# CONNECTOR_B.net
KiCad netlist of a schematic drawn in Altium Designer
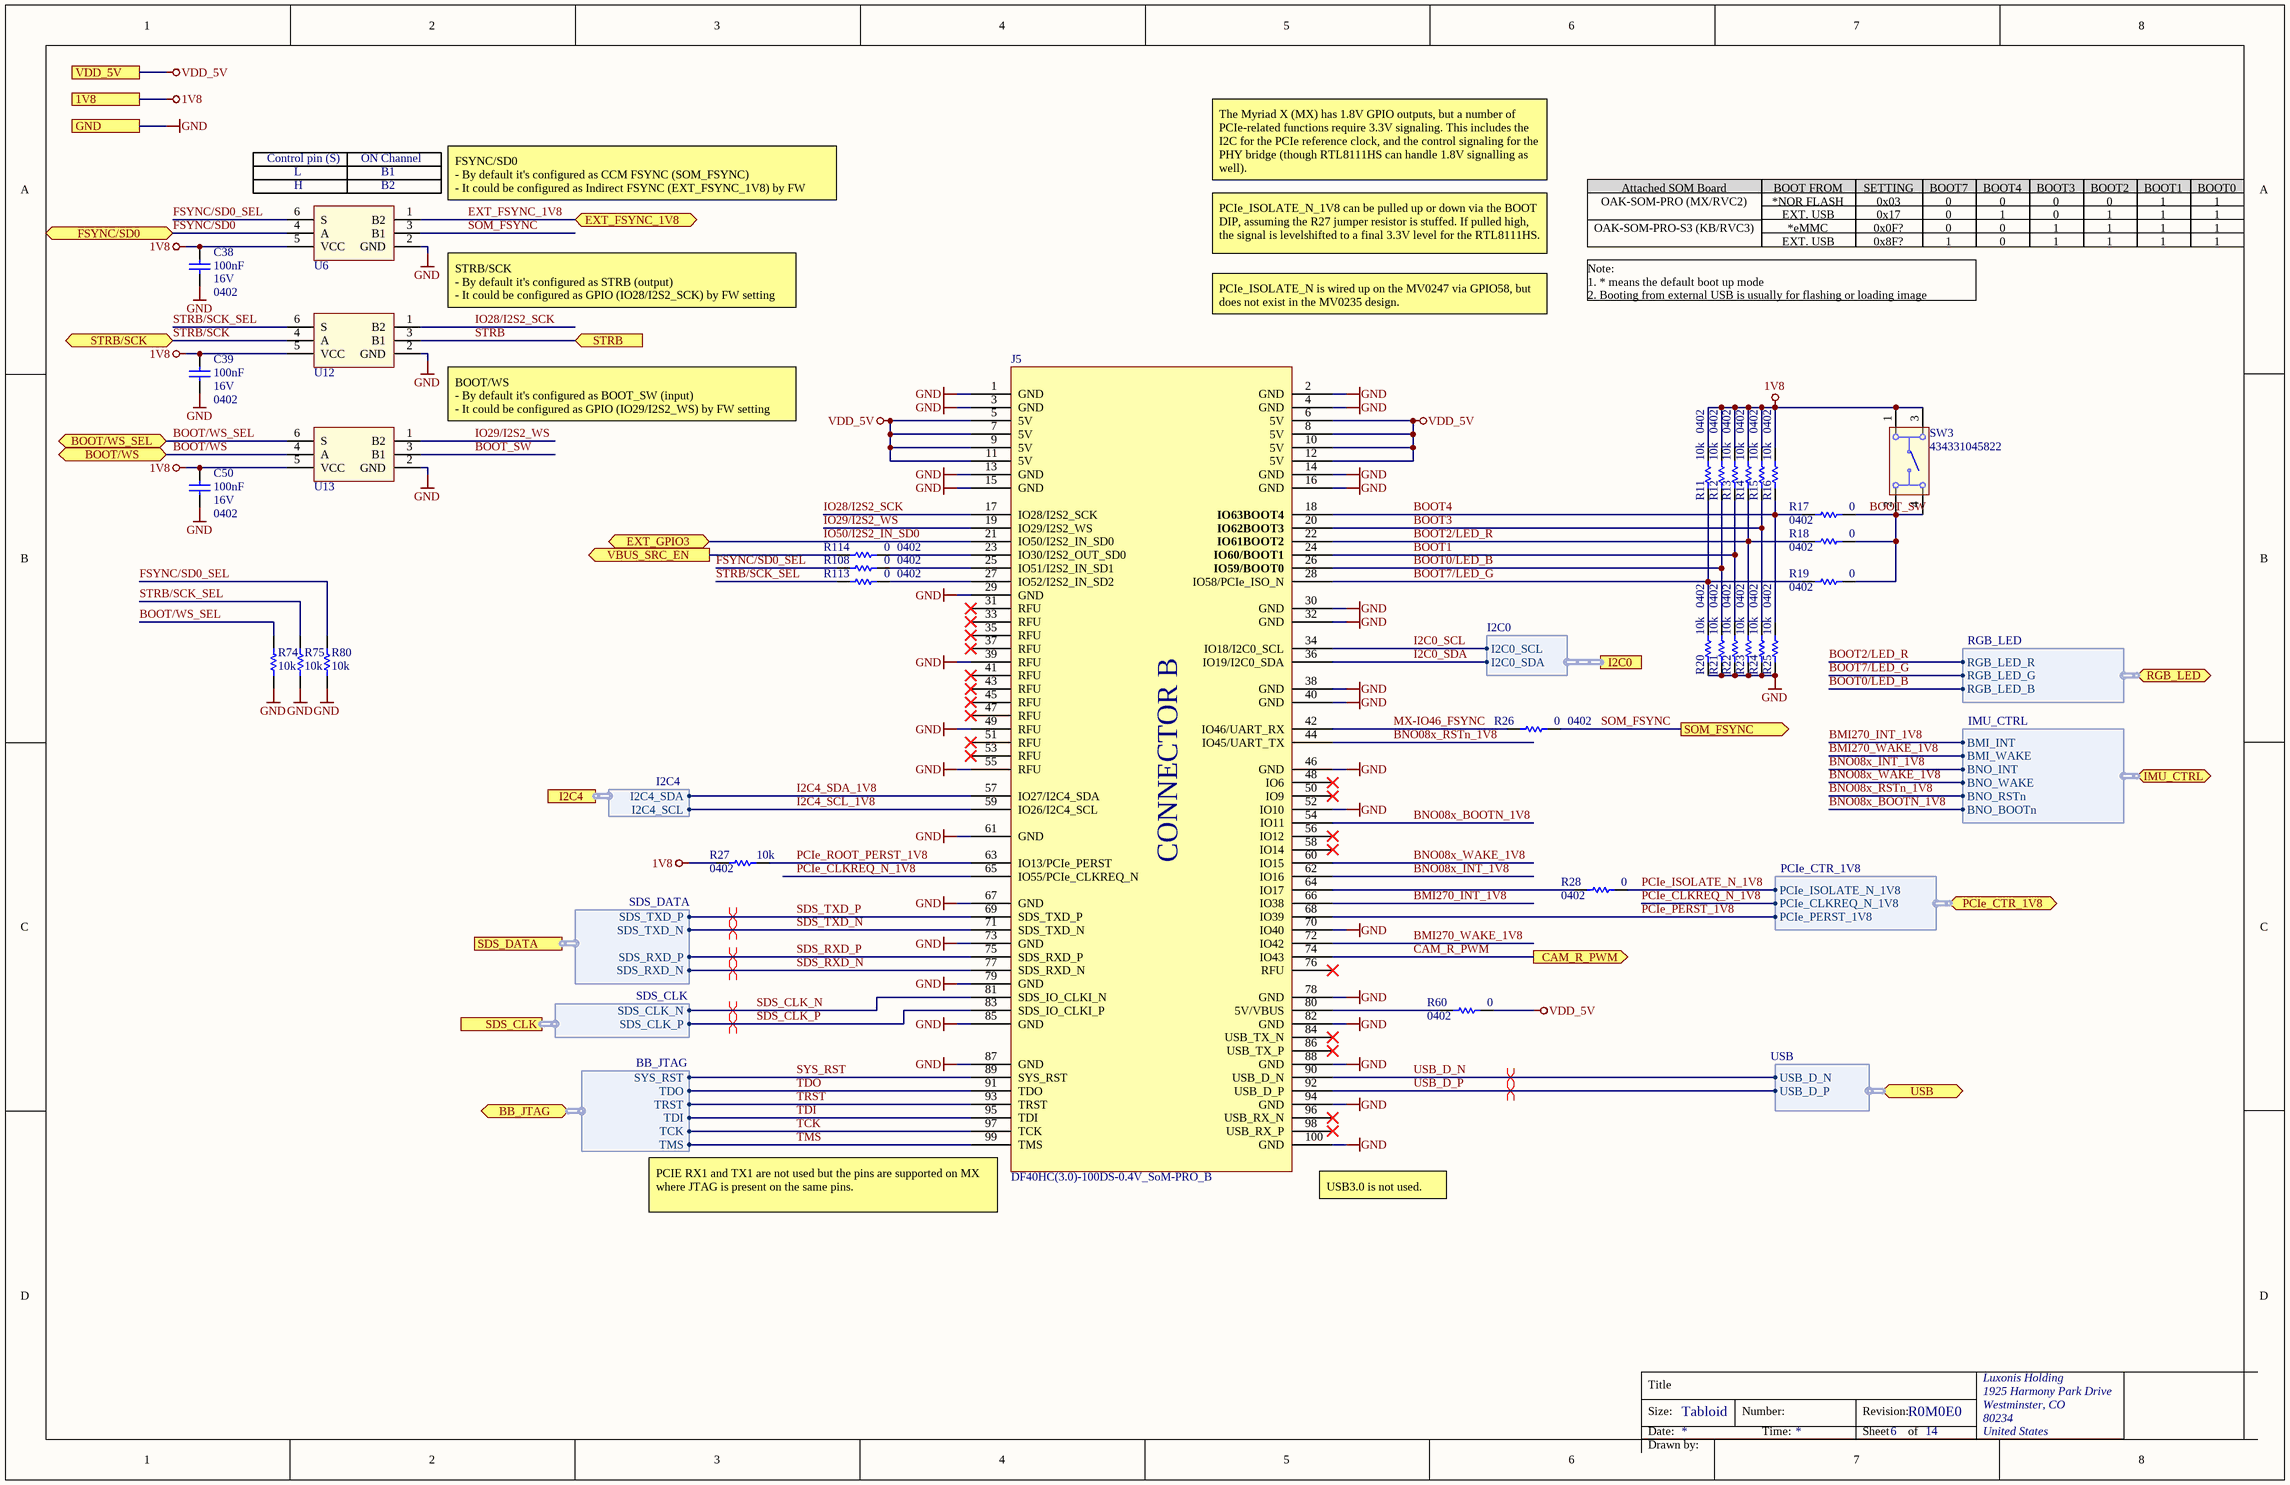
[diagram p0: CONNECTOR_B.SchDoc]

(export (version "E")
  (design (tool "Eeschema 10.0.6"))
  (components
    (comp (ref "C38")
      (value "100nF")
      (footprint "CAPC0402(1005)60_N")
      (description "CAP CER 0.1UF 16V X7R 0402 10%")
      (fields
        (field (name "VOLTAGE RATING") "16V")
        (field (name "CASE/PACKAGE") "0402")
        (field (name "TOLERANCE") "10%")
        (field (name "Comment") "CL05B104KO5NFNC")
      )
      (libsource (lib "Luxonis LLC") (part "GRM188R61C475KAAJD"))
    )
    (comp (ref "C39")
      (value "100nF")
      (footprint "CAPC0402(1005)60_N")
      (description "CAP CER 0.1UF 16V X7R 0402 10%")
      (fields
        (field (name "VOLTAGE RATING") "16V")
        (field (name "CASE/PACKAGE") "0402")
        (field (name "TOLERANCE") "10%")
        (field (name "Comment") "CL05B104KO5NFNC")
      )
      (libsource (lib "Luxonis LLC") (part "GRM188R61C475KAAJD"))
    )
    (comp (ref "C50")
      (value "100nF")
      (footprint "CAPC0402(1005)60_N")
      (description "CAP CER 0.1UF 16V X7R 0402 10%")
      (fields
        (field (name "VOLTAGE RATING") "16V")
        (field (name "CASE/PACKAGE") "0402")
        (field (name "TOLERANCE") "10%")
        (field (name "Comment") "CL05B104KO5NFNC")
      )
      (libsource (lib "Luxonis LLC") (part "GRM188R61C475KAAJD"))
    )
    (comp (ref "J5")
      (value "DF40HC(3.0)-100DS-0.4V_SoM-PRO_B")
      (footprint "CON_B_BW2099_SoM_DF40HC-3.0-100DS-0.4V_minpad")
      (description "OAK-SoM-Pro base board conn. B")
      (libsource (lib "Luxonis LLC") (part "DF40HC(3.0)-100DS-0.4V_SoM-PRO_B"))
    )
    (comp (ref "R11")
      (value "10k")
      (footprint "RESC0402(1005)_N")
      (description "RES SMD 10K OHM 1% 1/16W 0402")
      (fields
        (field (name "CASE/PACKAGE") "0402")
        (field (name "TOLERANCE") "1%")
        (field (name "Comment") "RC0402FR-1310KL")
      )
      (libsource (lib "Luxonis LLC") (part "RC0402FR-0722RL_1"))
    )
    (comp (ref "R12")
      (value "10k")
      (footprint "RESC0402(1005)_N")
      (description "RES SMD 10K OHM 1% 1/16W 0402")
      (fields
        (field (name "CASE/PACKAGE") "0402")
        (field (name "TOLERANCE") "1%")
        (field (name "Comment") "RC0402FR-1310KL")
      )
      (libsource (lib "Luxonis LLC") (part "RC0402FR-0722RL_1"))
    )
    (comp (ref "R13")
      (value "10k")
      (footprint "RESC0402(1005)_N")
      (description "RES SMD 10K OHM 1% 1/16W 0402")
      (fields
        (field (name "CASE/PACKAGE") "0402")
        (field (name "TOLERANCE") "1%")
        (field (name "Comment") "RC0402FR-1310KL")
      )
      (libsource (lib "Luxonis LLC") (part "RC0402FR-0722RL_1"))
    )
    (comp (ref "R14")
      (value "10k")
      (footprint "RESC0402(1005)_N")
      (description "RES SMD 10K OHM 1% 1/16W 0402")
      (fields
        (field (name "CASE/PACKAGE") "0402")
        (field (name "TOLERANCE") "1%")
        (field (name "Comment") "RC0402FR-1310KL")
      )
      (libsource (lib "Luxonis LLC") (part "RC0402FR-0722RL_1"))
    )
    (comp (ref "R15")
      (value "10k")
      (footprint "RESC0402(1005)_N")
      (description "RES SMD 10K OHM 1% 1/16W 0402")
      (fields
        (field (name "CASE/PACKAGE") "0402")
        (field (name "TOLERANCE") "1%")
        (field (name "Comment") "RC0402FR-1310KL")
      )
      (libsource (lib "Luxonis LLC") (part "RC0402FR-0722RL_1"))
    )
    (comp (ref "R16")
      (value "10k")
      (footprint "RESC0402(1005)_N")
      (description "RES SMD 10K OHM 1% 1/16W 0402")
      (fields
        (field (name "CASE/PACKAGE") "0402")
        (field (name "TOLERANCE") "1%")
        (field (name "Comment") "RC0402FR-1310KL")
      )
      (libsource (lib "Luxonis LLC") (part "RC0402FR-0722RL_1"))
    )
    (comp (ref "R17")
      (value "0")
      (footprint "RESC0402(1005)_L")
      (description "RES SMD 0 OHM 5% 1/16W 0402")
      (fields
        (field (name "CASE/PACKAGE") "0402")
        (field (name "TOLERANCE") "5%")
        (field (name "Comment") "CRCW04020000Z0ED")
      )
      (libsource (lib "Luxonis LLC") (part "Default resistor symbol"))
    )
    (comp (ref "R18")
      (value "0")
      (footprint "RESC0402(1005)_L")
      (description "RES SMD 0 OHM 5% 1/16W 0402")
      (fields
        (field (name "CASE/PACKAGE") "0402")
        (field (name "TOLERANCE") "5%")
        (field (name "Comment") "CRCW04020000Z0ED")
      )
      (libsource (lib "Luxonis LLC") (part "Default resistor symbol"))
    )
    (comp (ref "R19")
      (value "0")
      (footprint "RESC0402(1005)_L")
      (description "RES SMD 0 OHM 5% 1/16W 0402")
      (fields
        (field (name "CASE/PACKAGE") "0402")
        (field (name "TOLERANCE") "5%")
        (field (name "Comment") "CRCW04020000Z0ED")
      )
      (libsource (lib "Luxonis LLC") (part "Default resistor symbol"))
    )
    (comp (ref "R20")
      (value "10k")
      (footprint "RESC0402(1005)_N")
      (description "RES SMD 10K OHM 1% 1/16W 0402")
      (fields
        (field (name "CASE/PACKAGE") "0402")
        (field (name "TOLERANCE") "1%")
        (field (name "Comment") "RC0402FR-1310KL")
      )
      (libsource (lib "Luxonis LLC") (part "RC0402FR-0722RL_1"))
    )
    (comp (ref "R21")
      (value "10k")
      (footprint "RESC0402(1005)_N")
      (description "RES SMD 10K OHM 1% 1/16W 0402")
      (fields
        (field (name "CASE/PACKAGE") "0402")
        (field (name "TOLERANCE") "1%")
        (field (name "Comment") "RC0402FR-1310KL")
      )
      (libsource (lib "Luxonis LLC") (part "RC0402FR-0722RL_1"))
    )
    (comp (ref "R22")
      (value "10k")
      (footprint "RESC0402(1005)_N")
      (description "RES SMD 10K OHM 1% 1/16W 0402")
      (fields
        (field (name "CASE/PACKAGE") "0402")
        (field (name "TOLERANCE") "1%")
        (field (name "Comment") "RC0402FR-1310KL")
      )
      (libsource (lib "Luxonis LLC") (part "RC0402FR-0722RL_1"))
    )
    (comp (ref "R23")
      (value "10k")
      (footprint "RESC0402(1005)_N")
      (description "RES SMD 10K OHM 1% 1/16W 0402")
      (fields
        (field (name "CASE/PACKAGE") "0402")
        (field (name "TOLERANCE") "1%")
        (field (name "Comment") "RC0402FR-1310KL")
      )
      (libsource (lib "Luxonis LLC") (part "RC0402FR-0722RL_1"))
    )
    (comp (ref "R24")
      (value "10k")
      (footprint "RESC0402(1005)_N")
      (description "RES SMD 10K OHM 1% 1/16W 0402")
      (fields
        (field (name "CASE/PACKAGE") "0402")
        (field (name "TOLERANCE") "1%")
        (field (name "Comment") "RC0402FR-1310KL")
      )
      (libsource (lib "Luxonis LLC") (part "RC0402FR-0722RL_1"))
    )
    (comp (ref "R25")
      (value "10k")
      (footprint "RESC0402(1005)_N")
      (description "RES SMD 10K OHM 1% 1/16W 0402")
      (fields
        (field (name "CASE/PACKAGE") "0402")
        (field (name "TOLERANCE") "1%")
        (field (name "Comment") "RC0402FR-1310KL")
      )
      (libsource (lib "Luxonis LLC") (part "RC0402FR-0722RL_1"))
    )
    (comp (ref "R26")
      (value "0")
      (footprint "RESC0402(1005)_L")
      (description "RES SMD 0 OHM 5% 1/16W 0402")
      (fields
        (field (name "CASE/PACKAGE") "0402")
        (field (name "TOLERANCE") "5%")
        (field (name "Comment") "CRCW04020000Z0ED")
      )
      (libsource (lib "Luxonis LLC") (part "Default resistor symbol"))
    )
    (comp (ref "R27")
      (value "10k")
      (footprint "RESC0402(1005)_N")
      (description "RES SMD 10K OHM 1% 1/16W 0402")
      (fields
        (field (name "CASE/PACKAGE") "0402")
        (field (name "TOLERANCE") "1%")
        (field (name "Comment") "RC0402FR-1310KL")
      )
      (libsource (lib "Luxonis LLC") (part "RC0402FR-0722RL_1"))
    )
    (comp (ref "R28")
      (value "0")
      (footprint "RESC0402(1005)_L")
      (description "RES SMD 0 OHM 5% 1/16W 0402")
      (fields
        (field (name "CASE/PACKAGE") "0402")
        (field (name "TOLERANCE") "5%")
        (field (name "Comment") "CRCW04020000Z0ED")
      )
      (libsource (lib "Luxonis LLC") (part "Default resistor symbol"))
    )
    (comp (ref "R60")
      (value "0")
      (footprint "RESC0402(1005)_L")
      (description "RES SMD 0 OHM 5% 1/16W 0402")
      (fields
        (field (name "CASE/PACKAGE") "0402")
        (field (name "TOLERANCE") "5%")
        (field (name "Comment") "CRCW04020000Z0ED")
      )
      (libsource (lib "Luxonis LLC") (part "Default resistor symbol"))
    )
    (comp (ref "R74")
      (value "10k")
      (footprint "RESC0402(1005)_N")
      (description "RES SMD 10K OHM 1% 1/16W 0402")
      (fields (field (name "TOLERANCE") "1%") (field (name "Comment") "RC0402FR-1310KL"))
      (libsource (lib "Luxonis LLC") (part "RC0402FR-0722RL_1"))
    )
    (comp (ref "R75")
      (value "10k")
      (footprint "RESC0402(1005)_N")
      (description "RES SMD 10K OHM 1% 1/16W 0402")
      (fields (field (name "TOLERANCE") "1%") (field (name "Comment") "RC0402FR-1310KL"))
      (libsource (lib "Luxonis LLC") (part "RC0402FR-0722RL_1"))
    )
    (comp (ref "R80")
      (value "10k")
      (footprint "RESC0402(1005)_N")
      (description "RES SMD 10K OHM 1% 1/16W 0402")
      (fields (field (name "TOLERANCE") "1%") (field (name "Comment") "RC0402FR-1310KL"))
      (libsource (lib "Luxonis LLC") (part "RC0402FR-0722RL_1"))
    )
    (comp (ref "R108")
      (value "0")
      (footprint "RESC0402(1005)_L")
      (description "RES SMD 0 OHM 5% 1/16W 0402")
      (fields
        (field (name "CASE/PACKAGE") "0402")
        (field (name "TOLERANCE") "5%")
        (field (name "Comment") "CRCW04020000Z0ED")
      )
      (libsource (lib "Luxonis LLC") (part "Default resistor symbol"))
    )
    (comp (ref "R113")
      (value "0")
      (footprint "RESC0402(1005)_L")
      (description "RES SMD 0 OHM 5% 1/16W 0402")
      (fields
        (field (name "CASE/PACKAGE") "0402")
        (field (name "TOLERANCE") "5%")
        (field (name "Comment") "CRCW04020000Z0ED")
      )
      (libsource (lib "Luxonis LLC") (part "Default resistor symbol"))
    )
    (comp (ref "R114")
      (value "0")
      (footprint "RESC0402(1005)_L")
      (description "RES SMD 0 OHM 5% 1/16W 0402")
      (fields
        (field (name "CASE/PACKAGE") "0402")
        (field (name "TOLERANCE") "5%")
        (field (name "Comment") "CRCW04020000Z0ED")
      )
      (libsource (lib "Luxonis LLC") (part "Default resistor symbol"))
    )
    (comp (ref "SW3")
      (value "434331045822")
      (footprint "434331045822")
      (libsource (lib "Luxonis LLC") (part "WE-TACT-SW-4"))
    )
    (comp (ref "U6")
      (value "SN74LVC1G3157DCKR")
      (footprint "DCK6_65")
      (description "IC SWITCH SPDT SC70-6 1 Circuit IC Switch 2:1 15Ohm SC-70-6")
      (libsource (lib "Luxonis LLC") (part "SN74LVC1G3157DCKR"))
    )
    (comp (ref "U12")
      (value "SN74LVC1G3157DCKR")
      (footprint "DCK6_65")
      (description "IC SWITCH SPDT SC70-6 1 Circuit IC Switch 2:1 15Ohm SC-70-6")
      (libsource (lib "Luxonis LLC") (part "SN74LVC1G3157DCKR"))
    )
    (comp (ref "U13")
      (value "SN74LVC1G3157DCKR")
      (footprint "DCK6_65")
      (description "IC SWITCH SPDT SC70-6 1 Circuit IC Switch 2:1 15Ohm SC-70-6")
      (libsource (lib "Luxonis LLC") (part "SN74LVC1G3157DCKR"))
    )
  )
  (nets
    (net (code "10") (name "/BMI270_INT_1V8") (class "Default")
      (node (ref "J5") (pin "66") (pinfunction "IO38_66") (pintype "passive"))
    )
    (net (code "11") (name "/BMI270_WAKE_1V8") (class "Default")
      (node (ref "J5") (pin "72") (pinfunction "IO42_72") (pintype "passive"))
    )
    (net (code "12") (name "/BNO08x_BOOTN_1V8") (class "Default")
      (node (ref "J5") (pin "54") (pinfunction "IO11_54") (pintype "passive"))
    )
    (net (code "13") (name "/BNO08x_INT_1V8") (class "Default")
      (node (ref "J5") (pin "62") (pinfunction "IO16_62") (pintype "passive"))
    )
    (net (code "14") (name "/BNO08x_RSTn_1V8") (class "Default")
      (node (ref "J5") (pin "44") (pinfunction "IO45/UART_TX_44") (pintype "passive"))
    )
    (net (code "15") (name "/BNO08x_WAKE_1V8") (class "Default")
      (node (ref "J5") (pin "60") (pinfunction "IO15_60") (pintype "passive"))
    )
    (net (code "16") (name "/BOOT0{slash}LED_B") (class "Default")
      (node (ref "J5") (pin "26") (pinfunction "IO59/BOOT0_26") (pintype "passive"))
      (node (ref "R12") (pin "1") (pinfunction "1_1") (pintype "passive"))
      (node (ref "R21") (pin "2") (pinfunction "2_2") (pintype "passive"))
    )
    (net (code "17") (name "/BOOT1") (class "Default")
      (node (ref "J5") (pin "24") (pinfunction "IO60/BOOT1_24") (pintype "passive"))
      (node (ref "R13") (pin "1") (pinfunction "1_1") (pintype "passive"))
      (node (ref "R22") (pin "2") (pinfunction "2_2") (pintype "passive"))
    )
    (net (code "18") (name "/BOOT2{slash}LED_R") (class "Default")
      (node (ref "J5") (pin "22") (pinfunction "IO61BOOT2_22") (pintype "passive"))
      (node (ref "R14") (pin "1") (pinfunction "1_1") (pintype "passive"))
      (node (ref "R18") (pin "1") (pinfunction "1_1") (pintype "passive"))
      (node (ref "R23") (pin "2") (pinfunction "2_2") (pintype "passive"))
    )
    (net (code "19") (name "/BOOT3") (class "Default")
      (node (ref "J5") (pin "20") (pinfunction "IO62BOOT3_20") (pintype "passive"))
      (node (ref "R15") (pin "1") (pinfunction "1_1") (pintype "passive"))
      (node (ref "R24") (pin "2") (pinfunction "2_2") (pintype "passive"))
    )
    (net (code "20") (name "/BOOT4") (class "Default")
      (node (ref "J5") (pin "18") (pinfunction "IO63BOOT4_18") (pintype "passive"))
      (node (ref "R16") (pin "1") (pinfunction "1_1") (pintype "passive"))
      (node (ref "R17") (pin "1") (pinfunction "1_1") (pintype "passive"))
      (node (ref "R25") (pin "2") (pinfunction "2_2") (pintype "passive"))
    )
    (net (code "21") (name "/BOOT7{slash}LED_G") (class "Default")
      (node (ref "J5") (pin "28") (pinfunction "IO58/PCIe_ISO_N_28") (pintype "passive"))
      (node (ref "R11") (pin "1") (pinfunction "1_1") (pintype "passive"))
      (node (ref "R19") (pin "1") (pinfunction "1_1") (pintype "passive"))
      (node (ref "R20") (pin "2") (pinfunction "2_2") (pintype "passive"))
    )
    (net (code "22") (name "/BOOT_SW") (class "Default")
      (node (ref "R17") (pin "2") (pinfunction "2_2") (pintype "passive"))
      (node (ref "R18") (pin "2") (pinfunction "2_2") (pintype "passive"))
      (node (ref "R19") (pin "2") (pinfunction "2_2") (pintype "passive"))
      (node (ref "SW3") (pin "2") (pinfunction "2_2") (pintype "passive"))
      (node (ref "SW3") (pin "4") (pinfunction "4_4") (pintype "passive"))
      (node (ref "U13") (pin "3") (pinfunction "B1_3") (pintype "passive"))
    )
    (net (code "23") (name "/BOOT{slash}WS") (class "Default")
      (node (ref "U13") (pin "4") (pinfunction "A_4") (pintype "passive"))
    )
    (net (code "24") (name "/BOOT{slash}WS_SEL") (class "Default")
      (node (ref "R74") (pin "2") (pinfunction "2_2") (pintype "passive"))
      (node (ref "U13") (pin "6") (pinfunction "S_6") (pintype "passive"))
    )
    (net (code "25") (name "/CAM_R_PWM") (class "Default")
      (node (ref "J5") (pin "74") (pinfunction "IO43_74") (pintype "passive"))
    )
    (net (code "26") (name "/EXT_FSYNC_1V8") (class "Default")
      (node (ref "U6") (pin "1") (pinfunction "B2_1") (pintype "passive"))
    )
    (net (code "27") (name "/FSYNC{slash}SD0") (class "Default")
      (node (ref "U6") (pin "4") (pinfunction "A_4") (pintype "passive"))
    )
    (net (code "28") (name "/FSYNC{slash}SD0_SEL") (class "Default")
      (node (ref "R108") (pin "1") (pinfunction "1_1") (pintype "passive"))
      (node (ref "R80") (pin "2") (pinfunction "2_2") (pintype "passive"))
      (node (ref "U6") (pin "6") (pinfunction "S_6") (pintype "passive"))
    )
    (net (code "29") (name "/I2C0_SCL") (class "Default")
      (node (ref "J5") (pin "34") (pinfunction "IO18/I2C0_SCL_34") (pintype "passive"))
    )
    (net (code "30") (name "/I2C0_SDA") (class "Default")
      (node (ref "J5") (pin "36") (pinfunction "IO19/I2C0_SDA_36") (pintype "passive"))
    )
    (net (code "31") (name "/I2C4_SCL_1V8") (class "Default")
      (node (ref "J5") (pin "59") (pinfunction "IO26/I2C4_SCL_59") (pintype "passive"))
    )
    (net (code "32") (name "/I2C4_SDA_1V8") (class "Default")
      (node (ref "J5") (pin "57") (pinfunction "IO27/I2C4_SDA_57") (pintype "passive"))
    )
    (net (code "33") (name "/IO28{slash}I2S2_SCK") (class "Default")
      (node (ref "J5") (pin "17") (pinfunction "IO28/I2S2_SCK_17") (pintype "passive"))
      (node (ref "U12") (pin "1") (pinfunction "B2_1") (pintype "passive"))
    )
    (net (code "34") (name "/IO29{slash}I2S2_WS") (class "Default")
      (node (ref "J5") (pin "19") (pinfunction "IO29/I2S2_WS_19") (pintype "passive"))
      (node (ref "U13") (pin "1") (pinfunction "B2_1") (pintype "passive"))
    )
    (net (code "35") (name "/IO50{slash}I2S2_IN_SD0") (class "Default")
      (node (ref "J5") (pin "21") (pinfunction "IO50/I2S2_IN_SD0_21") (pintype "passive"))
    )
    (net (code "36") (name "/MX-IO46_FSYNC") (class "Default")
      (node (ref "J5") (pin "42") (pinfunction "IO46/UART_RX_42") (pintype "passive"))
      (node (ref "R26") (pin "1") (pinfunction "1_1") (pintype "passive"))
    )
    (net (code "37") (name "/PCIe_CLKREQ_N_1V8") (class "Default")
      (node (ref "J5") (pin "65") (pinfunction "IO55/PCIe_CLKREQ_N_65") (pintype "passive"))
    )
    (net (code "38") (name "/PCIe_ISOLATE_N_1V8") (class "Default")
      (node (ref "R28") (pin "2") (pinfunction "2_2") (pintype "passive"))
    )
    (net (code "39") (name "/PCIe_PERST_1V8") (class "Default")
      (node (ref "J5") (pin "68") (pinfunction "IO39_68") (pintype "passive"))
    )
    (net (code "40") (name "/PCIe_ROOT_PERST_1V8") (class "Default")
      (node (ref "J5") (pin "63") (pinfunction "IO13/PCIe_PERST_63") (pintype "passive"))
      (node (ref "R27") (pin "1") (pinfunction "1_1") (pintype "passive"))
    )
    (net (code "41") (name "/SDS_CLK_N") (class "Default")
      (node (ref "J5") (pin "81") (pinfunction "SDS_IO_CLKI_N_81") (pintype "passive"))
    )
    (net (code "42") (name "/SDS_CLK_P") (class "Default")
      (node (ref "J5") (pin "83") (pinfunction "SDS_IO_CLKI_P_83") (pintype "passive"))
    )
    (net (code "43") (name "/SDS_RXD_N") (class "Default")
      (node (ref "J5") (pin "77") (pinfunction "SDS_RXD_N_77") (pintype "passive"))
    )
    (net (code "44") (name "/SDS_RXD_P") (class "Default")
      (node (ref "J5") (pin "75") (pinfunction "SDS_RXD_P_75") (pintype "passive"))
    )
    (net (code "45") (name "/SDS_TXD_N") (class "Default")
      (node (ref "J5") (pin "71") (pinfunction "SDS_TXD_N_71") (pintype "passive"))
    )
    (net (code "46") (name "/SDS_TXD_P") (class "Default")
      (node (ref "J5") (pin "69") (pinfunction "SDS_TXD_P_69") (pintype "passive"))
    )
    (net (code "47") (name "/SOM_FSYNC") (class "Default")
      (node (ref "R26") (pin "2") (pinfunction "2_2") (pintype "passive"))
      (node (ref "U6") (pin "3") (pinfunction "B1_3") (pintype "passive"))
    )
    (net (code "48") (name "/STRB") (class "Default")
      (node (ref "U12") (pin "3") (pinfunction "B1_3") (pintype "passive"))
    )
    (net (code "49") (name "/STRB{slash}SCK") (class "Default")
      (node (ref "U12") (pin "4") (pinfunction "A_4") (pintype "passive"))
    )
    (net (code "50") (name "/STRB{slash}SCK_SEL") (class "Default")
      (node (ref "R113") (pin "1") (pinfunction "1_1") (pintype "passive"))
      (node (ref "R75") (pin "2") (pinfunction "2_2") (pintype "passive"))
      (node (ref "U12") (pin "6") (pinfunction "S_6") (pintype "passive"))
    )
    (net (code "51") (name "/SYS_RST") (class "Default")
      (node (ref "J5") (pin "89") (pinfunction "SYS_RST_89") (pintype "passive"))
    )
    (net (code "52") (name "/TCK") (class "Default")
      (node (ref "J5") (pin "97") (pinfunction "TCK_97") (pintype "passive"))
    )
    (net (code "53") (name "/TDI") (class "Default")
      (node (ref "J5") (pin "95") (pinfunction "TDI_95") (pintype "passive"))
    )
    (net (code "54") (name "/TDO") (class "Default")
      (node (ref "J5") (pin "91") (pinfunction "TDO_91") (pintype "passive"))
    )
    (net (code "55") (name "/TMS") (class "Default")
      (node (ref "J5") (pin "99") (pinfunction "TMS_99") (pintype "passive"))
    )
    (net (code "56") (name "/TRST") (class "Default")
      (node (ref "J5") (pin "93") (pinfunction "TRST_93") (pintype "passive"))
    )
    (net (code "57") (name "/USB_D_N") (class "Default")
      (node (ref "J5") (pin "90") (pinfunction "USB_D_N_90") (pintype "passive"))
    )
    (net (code "58") (name "/USB_D_P") (class "Default")
      (node (ref "J5") (pin "92") (pinfunction "USB_D_P_92") (pintype "passive"))
    )
    (net (code "59") (name "/VBUS_SRC_EN") (class "Default")
      (node (ref "R114") (pin "1") (pinfunction "1_1") (pintype "passive"))
    )
    (net (code "69") (name "1V8") (class "Default")
      (node (ref "C38") (pin "2") (pinfunction "2_2") (pintype "passive"))
      (node (ref "C39") (pin "2") (pinfunction "2_2") (pintype "passive"))
      (node (ref "C50") (pin "2") (pinfunction "2_2") (pintype "passive"))
      (node (ref "R11") (pin "2") (pinfunction "2_2") (pintype "passive"))
      (node (ref "R12") (pin "2") (pinfunction "2_2") (pintype "passive"))
      (node (ref "R13") (pin "2") (pinfunction "2_2") (pintype "passive"))
      (node (ref "R14") (pin "2") (pinfunction "2_2") (pintype "passive"))
      (node (ref "R15") (pin "2") (pinfunction "2_2") (pintype "passive"))
      (node (ref "R16") (pin "2") (pinfunction "2_2") (pintype "passive"))
      (node (ref "R27") (pin "2") (pinfunction "2_2") (pintype "passive"))
      (node (ref "SW3") (pin "1") (pinfunction "1_1") (pintype "passive"))
      (node (ref "SW3") (pin "3") (pinfunction "3_3") (pintype "passive"))
      (node (ref "U12") (pin "5") (pinfunction "VCC_5") (pintype "passive"))
      (node (ref "U13") (pin "5") (pinfunction "VCC_5") (pintype "passive"))
      (node (ref "U6") (pin "5") (pinfunction "VCC_5") (pintype "passive"))
    )
    (net (code "70") (name "GND") (class "Default")
      (node (ref "C38") (pin "1") (pinfunction "1_1") (pintype "passive"))
      (node (ref "C39") (pin "1") (pinfunction "1_1") (pintype "passive"))
      (node (ref "C50") (pin "1") (pinfunction "1_1") (pintype "passive"))
      (node (ref "J5") (pin "1") (pinfunction "GND_1") (pintype "passive"))
      (node (ref "J5") (pin "100") (pinfunction "GND_100") (pintype "passive"))
      (node (ref "J5") (pin "13") (pinfunction "GND_13") (pintype "passive"))
      (node (ref "J5") (pin "14") (pinfunction "GND_14") (pintype "passive"))
      (node (ref "J5") (pin "15") (pinfunction "GND_15") (pintype "passive"))
      (node (ref "J5") (pin "16") (pinfunction "GND_16") (pintype "passive"))
      (node (ref "J5") (pin "2") (pinfunction "GND_2") (pintype "passive"))
      (node (ref "J5") (pin "29") (pinfunction "GND_29") (pintype "passive"))
      (node (ref "J5") (pin "3") (pinfunction "GND_3") (pintype "passive"))
      (node (ref "J5") (pin "30") (pinfunction "GND_30") (pintype "passive"))
      (node (ref "J5") (pin "32") (pinfunction "GND_32") (pintype "passive"))
      (node (ref "J5") (pin "38") (pinfunction "GND_38") (pintype "passive"))
      (node (ref "J5") (pin "39") (pinfunction "RFU_39") (pintype "passive"))
      (node (ref "J5") (pin "4") (pinfunction "GND_4") (pintype "passive"))
      (node (ref "J5") (pin "40") (pinfunction "GND_40") (pintype "passive"))
      (node (ref "J5") (pin "46") (pinfunction "GND_46") (pintype "passive"))
      (node (ref "J5") (pin "49") (pinfunction "RFU_49") (pintype "passive"))
      (node (ref "J5") (pin "52") (pinfunction "IO10_52") (pintype "passive"))
      (node (ref "J5") (pin "55") (pinfunction "RFU_55") (pintype "passive"))
      (node (ref "J5") (pin "61") (pinfunction "GND_61") (pintype "passive"))
      (node (ref "J5") (pin "67") (pinfunction "GND_67") (pintype "passive"))
      (node (ref "J5") (pin "70") (pinfunction "IO40_70") (pintype "passive"))
      (node (ref "J5") (pin "73") (pinfunction "GND_73") (pintype "passive"))
      (node (ref "J5") (pin "78") (pinfunction "GND_78") (pintype "passive"))
      (node (ref "J5") (pin "79") (pinfunction "GND_79") (pintype "passive"))
      (node (ref "J5") (pin "82") (pinfunction "GND_82") (pintype "passive"))
      (node (ref "J5") (pin "85") (pinfunction "GND_85") (pintype "passive"))
      (node (ref "J5") (pin "87") (pinfunction "GND_87") (pintype "passive"))
      (node (ref "J5") (pin "88") (pinfunction "GND_88") (pintype "passive"))
      (node (ref "J5") (pin "94") (pinfunction "GND_94") (pintype "passive"))
      (node (ref "R20") (pin "1") (pinfunction "1_1") (pintype "passive"))
      (node (ref "R21") (pin "1") (pinfunction "1_1") (pintype "passive"))
      (node (ref "R22") (pin "1") (pinfunction "1_1") (pintype "passive"))
      (node (ref "R23") (pin "1") (pinfunction "1_1") (pintype "passive"))
      (node (ref "R24") (pin "1") (pinfunction "1_1") (pintype "passive"))
      (node (ref "R25") (pin "1") (pinfunction "1_1") (pintype "passive"))
      (node (ref "R74") (pin "1") (pinfunction "1_1") (pintype "passive"))
      (node (ref "R75") (pin "1") (pinfunction "1_1") (pintype "passive"))
      (node (ref "R80") (pin "1") (pinfunction "1_1") (pintype "passive"))
      (node (ref "U12") (pin "2") (pinfunction "GND_2") (pintype "passive"))
      (node (ref "U13") (pin "2") (pinfunction "GND_2") (pintype "passive"))
      (node (ref "U6") (pin "2") (pinfunction "GND_2") (pintype "passive"))
    )
    (net (code "71") (name "Net-(J5-5V{slash}VBUS)") (class "Default")
      (node (ref "J5") (pin "80") (pinfunction "5V/VBUS_80") (pintype "passive"))
      (node (ref "R60") (pin "1") (pinfunction "1_1") (pintype "passive"))
    )
    (net (code "72") (name "Net-(J5-IO17)") (class "Default")
      (node (ref "J5") (pin "64") (pinfunction "IO17_64") (pintype "passive"))
      (node (ref "R28") (pin "1") (pinfunction "1_1") (pintype "passive"))
    )
    (net (code "73") (name "Net-(J5-IO30{slash}I2S2_OUT_SD0)") (class "Default")
      (node (ref "J5") (pin "23") (pinfunction "IO30/I2S2_OUT_SD0_23") (pintype "passive"))
      (node (ref "R114") (pin "2") (pinfunction "2_2") (pintype "passive"))
    )
    (net (code "74") (name "Net-(J5-IO51{slash}I2S2_IN_SD1)") (class "Default")
      (node (ref "J5") (pin "25") (pinfunction "IO51/I2S2_IN_SD1_25") (pintype "passive"))
      (node (ref "R108") (pin "2") (pinfunction "2_2") (pintype "passive"))
    )
    (net (code "75") (name "Net-(J5-IO52{slash}I2S2_IN_SD2)") (class "Default")
      (node (ref "J5") (pin "27") (pinfunction "IO52/I2S2_IN_SD2_27") (pintype "passive"))
      (node (ref "R113") (pin "2") (pinfunction "2_2") (pintype "passive"))
    )
    (net (code "76") (name "VDD_5V") (class "Default")
      (node (ref "J5") (pin "10") (pinfunction "5V_10") (pintype "passive"))
      (node (ref "J5") (pin "11") (pinfunction "5V_11") (pintype "passive"))
      (node (ref "J5") (pin "12") (pinfunction "5V_12") (pintype "passive"))
      (node (ref "J5") (pin "5") (pinfunction "5V_5") (pintype "passive"))
      (node (ref "J5") (pin "6") (pinfunction "5V_6") (pintype "passive"))
      (node (ref "J5") (pin "7") (pinfunction "5V_7") (pintype "passive"))
      (node (ref "J5") (pin "8") (pinfunction "5V_8") (pintype "passive"))
      (node (ref "J5") (pin "9") (pinfunction "5V_9") (pintype "passive"))
      (node (ref "R60") (pin "2") (pinfunction "2_2") (pintype "passive"))
    )
    (net (code "77") (name "unconnected-(J5-IO6-Pad48)") (class "Default")
      (node (ref "J5") (pin "48") (pinfunction "IO6_48") (pintype "passive+no_connect"))
    )
    (net (code "78") (name "unconnected-(J5-IO9-Pad50)") (class "Default")
      (node (ref "J5") (pin "50") (pinfunction "IO9_50") (pintype "passive+no_connect"))
    )
    (net (code "79") (name "unconnected-(J5-IO12-Pad56)") (class "Default")
      (node (ref "J5") (pin "56") (pinfunction "IO12_56") (pintype "passive+no_connect"))
    )
    (net (code "80") (name "unconnected-(J5-IO14-Pad58)") (class "Default")
      (node (ref "J5") (pin "58") (pinfunction "IO14_58") (pintype "passive+no_connect"))
    )
    (net (code "81") (name "unconnected-(J5-RFU-Pad31)") (class "Default")
      (node (ref "J5") (pin "31") (pinfunction "RFU_31") (pintype "passive+no_connect"))
    )
    (net (code "82") (name "unconnected-(J5-RFU-Pad33)") (class "Default")
      (node (ref "J5") (pin "33") (pinfunction "RFU_33") (pintype "passive+no_connect"))
    )
    (net (code "83") (name "unconnected-(J5-RFU-Pad35)") (class "Default")
      (node (ref "J5") (pin "35") (pinfunction "RFU_35") (pintype "passive+no_connect"))
    )
    (net (code "84") (name "unconnected-(J5-RFU-Pad37)") (class "Default")
      (node (ref "J5") (pin "37") (pinfunction "RFU_37") (pintype "passive+no_connect"))
    )
    (net (code "85") (name "unconnected-(J5-RFU-Pad41)") (class "Default")
      (node (ref "J5") (pin "41") (pinfunction "RFU_41") (pintype "passive+no_connect"))
    )
    (net (code "86") (name "unconnected-(J5-RFU-Pad43)") (class "Default")
      (node (ref "J5") (pin "43") (pinfunction "RFU_43") (pintype "passive+no_connect"))
    )
    (net (code "87") (name "unconnected-(J5-RFU-Pad45)") (class "Default")
      (node (ref "J5") (pin "45") (pinfunction "RFU_45") (pintype "passive+no_connect"))
    )
    (net (code "88") (name "unconnected-(J5-RFU-Pad47)") (class "Default")
      (node (ref "J5") (pin "47") (pinfunction "RFU_47") (pintype "passive+no_connect"))
    )
    (net (code "89") (name "unconnected-(J5-RFU-Pad51)") (class "Default")
      (node (ref "J5") (pin "51") (pinfunction "RFU_51") (pintype "passive+no_connect"))
    )
    (net (code "90") (name "unconnected-(J5-RFU-Pad53)") (class "Default")
      (node (ref "J5") (pin "53") (pinfunction "RFU_53") (pintype "passive+no_connect"))
    )
    (net (code "91") (name "unconnected-(J5-RFU-Pad76)") (class "Default")
      (node (ref "J5") (pin "76") (pinfunction "RFU_76") (pintype "passive+no_connect"))
    )
    (net (code "92") (name "unconnected-(J5-USB_RX_N-Pad96)") (class "Default")
      (node (ref "J5") (pin "96") (pinfunction "USB_RX_N_96") (pintype "passive+no_connect"))
    )
    (net (code "93") (name "unconnected-(J5-USB_RX_P-Pad98)") (class "Default")
      (node (ref "J5") (pin "98") (pinfunction "USB_RX_P_98") (pintype "passive+no_connect"))
    )
    (net (code "94") (name "unconnected-(J5-USB_TX_N-Pad84)") (class "Default")
      (node (ref "J5") (pin "84") (pinfunction "USB_TX_N_84") (pintype "passive+no_connect"))
    )
    (net (code "95") (name "unconnected-(J5-USB_TX_P-Pad86)") (class "Default")
      (node (ref "J5") (pin "86") (pinfunction "USB_TX_P_86") (pintype "passive+no_connect"))
    )
  )
)
